# Motor_Interface.net
KiCad netlist of a schematic drawn in Altium Designer
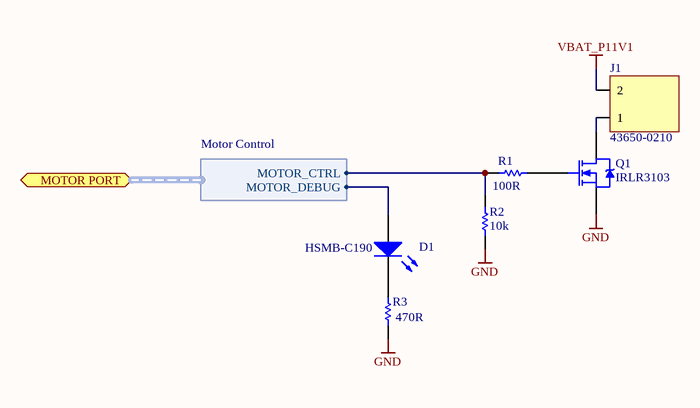
[diagram p0: Motor Interface.SchDoc]

(export (version "E")
  (design (tool "Eeschema 10.0.6"))
  (components
    (comp (ref "D1")
      (value "HSMB-C190")
      (footprint "1.6X0.8X0.8")
      (description "Blue Surface Mount Chip LED, Blue")
      (fields (field (name "PUBLISHER") "Altium Limited"))
      (libsource (lib "Avago Optoelectronic LED") (part "HSMB-C190"))
    )
    (comp (ref "J1")
      (value "43650-0210")
      (footprint "43650-0210")
      (description "Power Connector, Micro-Fit 3.0 Header, SMT, Single Row, Right Angle, 2 Circuits")
      (libsource (lib "Molex Power Connector") (part "43650-0210"))
    )
    (comp (ref "Q1")
      (value "IRLR3103")
      (footprint "TO-252AA_N")
      (description "HEXFET Power MOSFET")
      (fields (field (name "PUBLISHER") "Altium Limited"))
      (libsource (lib "IR Discrete MOSFET - Power") (part "IRLR3103"))
    )
    (comp (ref "R1")
      (value "100R")
      (footprint "3-0603")
      (description "Thick Film Chip Resistor, 1 Ohm to 10M Ohm Range, 5% Tolerance, 0603 Size, 0.1 W")
      (fields (field (name "Comment") "ERJ3GEYJ101V") (field (name "PUBLISHER") "Altium Limited"))
      (libsource (lib "Panasonic Resistor") (part "ERJ3GE"))
    )
    (comp (ref "R2")
      (value "10k")
      (footprint "3-0603")
      (description "Thick Film Chip Resistor, 1 Ohm to 10M Ohm Range, 5% Tolerance, 0603 Size, 0.1 W")
      (fields (field (name "Comment") "ERJ3GEYJ103V") (field (name "PUBLISHER") "Altium Limited"))
      (libsource (lib "Panasonic Resistor") (part "ERJ3GE"))
    )
    (comp (ref "R3")
      (value "470R")
      (footprint "3-0603")
      (description "Thick Film Chip Resistor, 1 Ohm to 10M Ohm Range, 5% Tolerance, 0603 Size, 0.1 W")
      (fields (field (name "Comment") "ERJ3GEYJ471V") (field (name "PUBLISHER") "Altium Limited"))
      (libsource (lib "Panasonic Resistor") (part "ERJ3GE"))
    )
  )
  (nets
    (net (code "3") (name "/MOTOR_CTRL") (class "Default")
      (node (ref "R1") (pin "1") (pinfunction "1_1") (pintype "passive"))
      (node (ref "R2") (pin "1") (pinfunction "1_1") (pintype "passive"))
    )
    (net (code "4") (name "/MOTOR_DEBUG") (class "Default")
      (node (ref "D1") (pin "1") (pinfunction "A_1") (pintype "passive"))
    )
    (net (code "6") (name "GND") (class "Default")
      (node (ref "Q1") (pin "3") (pinfunction "S_3") (pintype "passive"))
      (node (ref "R2") (pin "2") (pinfunction "2_2") (pintype "passive"))
      (node (ref "R3") (pin "1") (pinfunction "1_1") (pintype "passive"))
    )
    (net (code "7") (name "Net-(D1-K)") (class "Default")
      (node (ref "D1") (pin "2") (pinfunction "K_2") (pintype "passive"))
      (node (ref "R3") (pin "2") (pinfunction "2_2") (pintype "passive"))
    )
    (net (code "8") (name "Net-(Q1-D)") (class "Default")
      (node (ref "J1") (pin "1") (pinfunction "1_1") (pintype "power_in"))
      (node (ref "Q1") (pin "4") (pinfunction "D_4") (pintype "passive"))
    )
    (net (code "9") (name "Net-(Q1-G)") (class "Default")
      (node (ref "Q1") (pin "1") (pinfunction "G_1") (pintype "passive"))
      (node (ref "R1") (pin "2") (pinfunction "2_2") (pintype "passive"))
    )
    (net (code "10") (name "VBAT_P11V1") (class "Default")
      (node (ref "J1") (pin "2") (pinfunction "2_2") (pintype "power_in"))
    )
  )
)
